# SiLPA_RF_channel_preamp.net
KiCad netlist of a schematic drawn in Altium Designer
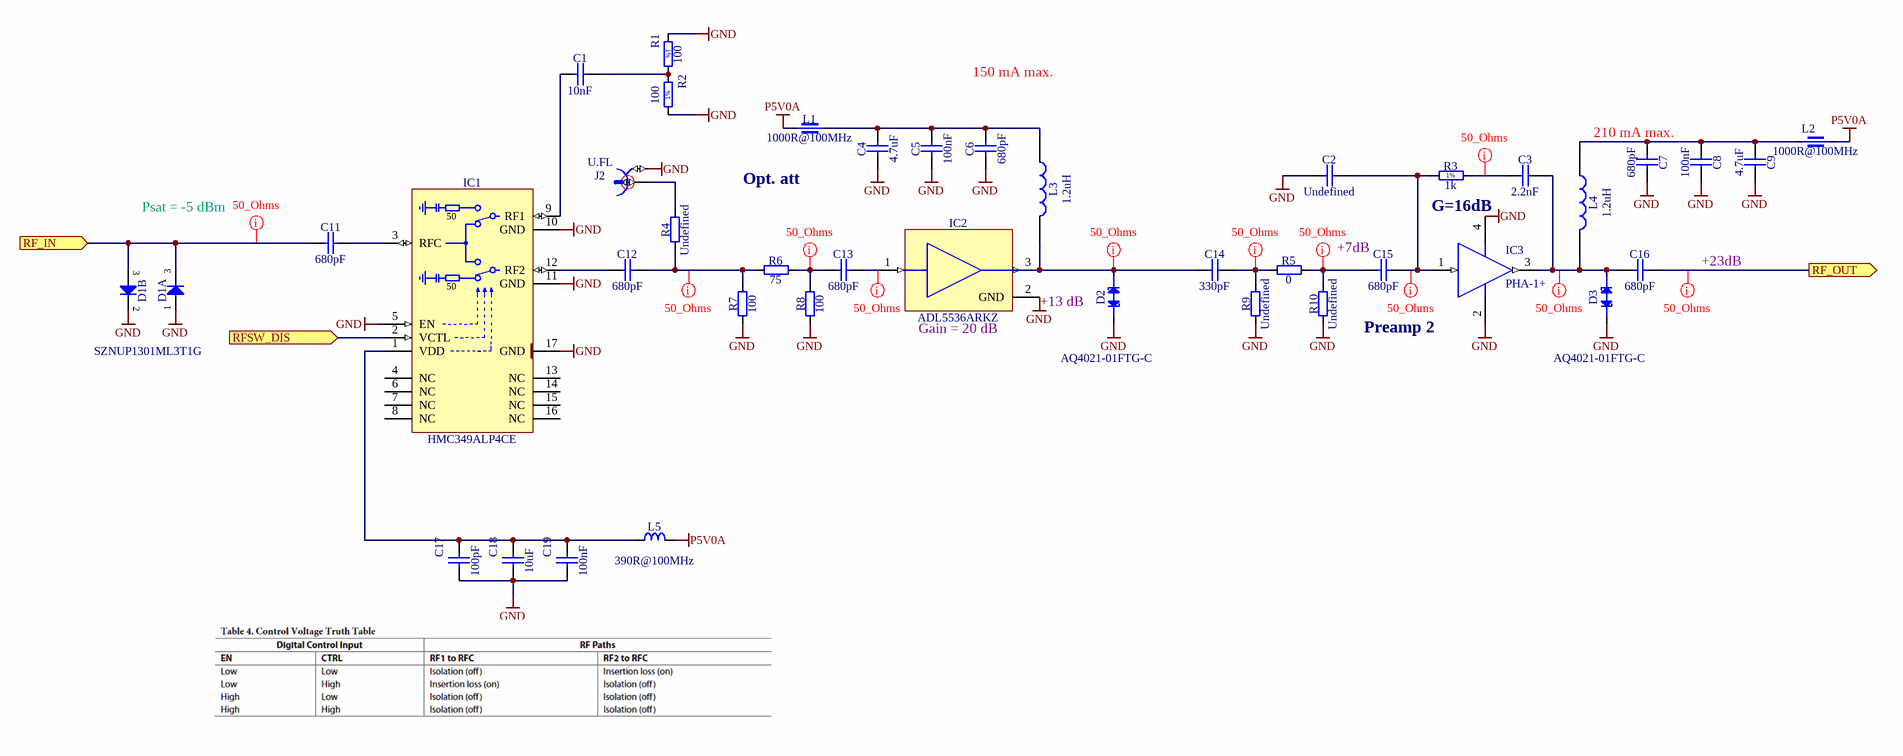
[diagram p0: SiLPA_RF_channel_preamp.SchDoc]

(export (version "E")
  (design (tool "Eeschema 10.0.6"))
  (components
    (comp (ref "C1")
      (value "10nF")
      (footprint "CAPC1005X55N")
      (description "Non-polarised capacitor")
      (fields
        (field (name "PART NUMBER") "CC0402_10NF_16V_10%_X7R")
        (field (name "VOLTAGE") "16V")
        (field (name "AUTHOR") "CERN DEM JLC")
      )
      (libsource (lib "Capacitors") (part "Capacitor - non polarized"))
    )
    (comp (ref "C2")
      (value "Undefined")
      (footprint "CAPC1608X90N")
      (description "Non-polarised capacitor")
      (fields (field (name "PART NUMBER") "CC0603_NO-VALUE") (field (name "AUTHOR") "CERN DEM MR"))
      (libsource (lib "Capacitors") (part "Capacitor - non polarized"))
    )
    (comp (ref "C3")
      (value "2.2nF")
      (footprint "CAPC1608X87N")
      (description "Non-polarised capacitor")
      (fields
        (field (name "PART NUMBER") "CC0603_2.2NF_50V_5%_C0G")
        (field (name "VOLTAGE") "50V")
        (field (name "AUTHOR") "CERN DEM JMW")
      )
      (libsource (lib "Capacitors") (part "Capacitor - non polarized"))
    )
    (comp (ref "C4")
      (value "4.7uF")
      (footprint "CAPC1709X95N")
      (description "Non-polarised capacitor")
      (fields
        (field (name "MANUFACTURER") "GENERIC")
        (field (name "MANUFACTURER PART NUMBER") "CC0603_4.7UF_16V_10%_X5R")
        (field (name "AUTHOR") "CERN DEM JLC")
      )
      (libsource (lib "Capacitors") (part "Capacitor - non polarized"))
    )
    (comp (ref "C5")
      (value "100nF")
      (footprint "CAPC1608X87N")
      (description "Non-polarised capacitor")
      (fields
        (field (name "MANUFACTURER") "GENERIC")
        (field (name "MANUFACTURER PART NUMBER") "CC0603_100NF_50V_10%_X7R")
        (field (name "AUTHOR") "CERN DEM JLC")
      )
      (libsource (lib "Capacitors") (part "Capacitor - non polarized"))
    )
    (comp (ref "C6")
      (value "680pF")
      (footprint "CAPC1608X87N")
      (description "Non-polarised capacitor")
      (fields
        (field (name "PART NUMBER") "CC0603_680PF_50V_5%_NP0")
        (field (name "VOLTAGE") "50V")
        (field (name "AUTHOR") "CERN DEM JLC")
      )
      (libsource (lib "Capacitors") (part "Capacitor - non polarized"))
    )
    (comp (ref "C7")
      (value "680pF")
      (footprint "CAPC1608X87N")
      (description "Non-polarised capacitor")
      (fields
        (field (name "MANUFACTURER") "GENERIC")
        (field (name "MANUFACTURER PART NUMBER") "CC0603_680PF_50V_5%_NP0")
        (field (name "AUTHOR") "CERN DEM JLC")
      )
      (libsource (lib "Capacitors") (part "Capacitor - non polarized"))
    )
    (comp (ref "C8")
      (value "100nF")
      (footprint "CAPC1608X87N")
      (description "Non-polarised capacitor")
      (fields
        (field (name "MANUFACTURER") "GENERIC")
        (field (name "MANUFACTURER PART NUMBER") "CC0603_100NF_50V_10%_X7R")
        (field (name "AUTHOR") "CERN DEM JLC")
      )
      (libsource (lib "Capacitors") (part "Capacitor - non polarized"))
    )
    (comp (ref "C9")
      (value "4.7uF")
      (footprint "CAPC1709X95N")
      (description "Non-polarised capacitor")
      (fields
        (field (name "MANUFACTURER") "GENERIC")
        (field (name "MANUFACTURER PART NUMBER") "CC0603_4.7UF_16V_10%_X5R")
        (field (name "AUTHOR") "CERN DEM JLC")
      )
      (libsource (lib "Capacitors") (part "Capacitor - non polarized"))
    )
    (comp (ref "C11")
      (value "680pF")
      (footprint "CAPC1608X87N")
      (description "Non-polarised capacitor")
      (fields
        (field (name "PART NUMBER") "CC0603_680PF_50V_5%_NP0")
        (field (name "VOLTAGE") "50V")
        (field (name "AUTHOR") "CERN DEM JLC")
      )
      (libsource (lib "Capacitors") (part "Capacitor - non polarized"))
    )
    (comp (ref "C12")
      (value "680pF")
      (footprint "CAPC1608X87N")
      (description "Non-polarised capacitor")
      (fields
        (field (name "PART NUMBER") "CC0603_680PF_50V_5%_NP0")
        (field (name "VOLTAGE") "50V")
        (field (name "AUTHOR") "CERN DEM JLC")
      )
      (libsource (lib "Capacitors") (part "Capacitor - non polarized"))
    )
    (comp (ref "C13")
      (value "680pF")
      (footprint "CAPC1608X87N")
      (description "Non-polarised capacitor")
      (fields
        (field (name "PART NUMBER") "CC0603_680PF_50V_5%_NP0")
        (field (name "VOLTAGE") "50V")
        (field (name "AUTHOR") "CERN DEM JLC")
      )
      (libsource (lib "Capacitors") (part "Capacitor - non polarized"))
    )
    (comp (ref "C14")
      (value "330pF")
      (footprint "CAPC1608X87N")
      (description "Non-polarised capacitor")
      (fields
        (field (name "MANUFACTURER") "GENERIC")
        (field (name "MANUFACTURER PART NUMBER") "CC0603_330PF_50V_1%_NP0")
        (field (name "AUTHOR") "CERN DEM MR")
      )
      (libsource (lib "Capacitors") (part "Capacitor - non polarized"))
    )
    (comp (ref "C15")
      (value "680pF")
      (footprint "CAPC1608X87N")
      (description "Non-polarised capacitor")
      (fields
        (field (name "MANUFACTURER") "GENERIC")
        (field (name "MANUFACTURER PART NUMBER") "CC0603_680PF_50V_5%_NP0")
        (field (name "AUTHOR") "CERN DEM JLC")
      )
      (libsource (lib "Capacitors") (part "Capacitor - non polarized"))
    )
    (comp (ref "C16")
      (value "680pF")
      (footprint "CAPC1608X87N")
      (description "Non-polarised capacitor")
      (fields
        (field (name "MANUFACTURER") "GENERIC")
        (field (name "MANUFACTURER PART NUMBER") "CC0603_680PF_50V_5%_NP0")
        (field (name "AUTHOR") "CERN DEM JLC")
      )
      (libsource (lib "Capacitors") (part "Capacitor - non polarized"))
    )
    (comp (ref "C17")
      (value "100pF")
      (footprint "CAPC1005X55N")
      (description "Non-polarised capacitor")
      (fields
        (field (name "PART NUMBER") "CC0402_100PF_50V_5%_C0G")
        (field (name "VOLTAGE") "50V")
        (field (name "AUTHOR") "CERN DEM JLC")
      )
      (libsource (lib "Capacitors") (part "Capacitor - non polarized"))
    )
    (comp (ref "C18")
      (value "10uF")
      (footprint "CAPC1608X80N")
      (description "Non-polarised capacitor")
      (fields
        (field (name "PART NUMBER") "CC0603_10UF_16V_20%_X5R")
        (field (name "VOLTAGE") "16V")
        (field (name "AUTHOR") "CERN DEM MR")
      )
      (libsource (lib "Capacitors") (part "Capacitor - non polarized"))
    )
    (comp (ref "C19")
      (value "100nF")
      (footprint "CAPC1005X55N")
      (description "Non-polarised capacitor")
      (fields
        (field (name "PART NUMBER") "CC0402_100NF_16V_10%_X5R")
        (field (name "VOLTAGE") "16V")
        (field (name "AUTHOR") "CERN DEM JLC")
      )
      (libsource (lib "Capacitors") (part "Capacitor - non polarized"))
    )
    (comp (ref "D1")
      (value "SZNUP1301ML3T1G")
      (footprint "SOT95P240X110-3N")
      (description "Low Capacitance Diode Array for ESD Protection in a Single Data Line")
      (fields (field (name "VOLTAGE") "70V") (field (name "POWER") "215mA") (field (name "AUTHOR") "GK"))
      (libsource (lib "Diodes") (part "D_TVS_SZNUP1301ML3T1G"))
    )
    (comp (ref "D2")
      (value "AQ4021-01FTG-C")
      (footprint "SOD2513X114N")
      (description "6V Bi-directional,ESD Protection for Transient Voltage Suppressor Diode")
      (fields (field (name "VOLTAGE") "6V") (field (name "POWER") "450W") (field (name "AUTHOR") "GK"))
      (libsource (lib "Diodes") (part "D_TVS_AQ4021-01FTG-C"))
    )
    (comp (ref "D3")
      (value "AQ4021-01FTG-C")
      (footprint "SOD2513X114N")
      (description "6V Bi-directional,ESD Protection for Transient Voltage Suppressor Diode")
      (fields (field (name "VOLTAGE") "6V") (field (name "POWER") "450W") (field (name "AUTHOR") "GK"))
      (libsource (lib "Diodes") (part "D_TVS_AQ4021-01FTG-C"))
    )
    (comp (ref "IC1")
      (value "HMC349ALP4CE")
      (footprint "QFN65P400X400X100-17N-S255")
      (description "DC-4GHz High Isolation SPDT Non-Reflective Switch")
      (fields (field (name "MANUFACTURER") "ANALOG DEVICES") (field (name "AUTHOR") "CERN DEM JLC"))
      (libsource (lib "ICs And Semiconductors") (part "HMC349ALP4CE"))
    )
    (comp (ref "IC2")
      (value "ADL5536ARKZ")
      (footprint "ANALOG-DEVICES_SOT-89(RK-3)")
      (description "20MHz to 1GHz IF Gain Block")
      (fields (field (name "MANUFACTURER") "ANALOG DEVICES") (field (name "AUTHOR") "CERN DEM BC"))
      (libsource (lib "ICs And Semiconductors") (part "ADL5536"))
    )
    (comp (ref "IC3")
      (value "PHA-1+")
      (footprint "MINI-CIRCUITS_DF782")
      (description "Monolithic Amplifier")
      (fields (field (name "MANUFACTURER") "MINI-CIRCUITS") (field (name "AUTHOR") "CERN DEM BC"))
      (libsource (lib "ICs And Semiconductors") (part "Monolithic Amplifier Type 1"))
    )
    (comp (ref "J2")
      (value "U.FL")
      (footprint "HIROSE_U.FL-R-SMT-1(10)")
      (fields
        (field (name "PART NUMBER") "HIROSE_U.FL-R-SMT-1(10)")
        (field (name "MANUFACTURER") "HIROSE (HRS)")
        (field (name "MANUFACTURER PART NUMBER") "U.FL-R-SMT-1(10)")
        (field (name "AUTHOR") "CERN DEM JLC")
      )
      (libsource (lib "Connectors") (part "Coax_1Male_1Shield"))
    )
    (comp (ref "L1")
      (value "1000R@100MHz")
      (footprint "INDC1608X95N")
      (fields
        (field (name "MANUFACTURER") "MURATA")
        (field (name "MANUFACTURER PART NUMBER") "BLM18HE102SN1")
        (field (name "PART NUMBER") "IND0603_MURATA_BLM18HE102SN1")
        (field (name "AUTHOR") "CERN DEM JLC")
      )
      (libsource (lib "Inductors & Transformers") (part "Ferrite Bead"))
    )
    (comp (ref "L2")
      (value "1000R@100MHz")
      (footprint "INDC1608X95N")
      (fields
        (field (name "MANUFACTURER") "MURATA")
        (field (name "MANUFACTURER PART NUMBER") "BLM18HE102SN1")
        (field (name "PART NUMBER") "IND0603_MURATA_BLM18HE102SN1")
        (field (name "AUTHOR") "CERN DEM JLC")
      )
      (libsource (lib "Inductors & Transformers") (part "Ferrite Bead"))
    )
    (comp (ref "L3")
      (value "1.2uH")
      (footprint "ADL2012S1R2MT01")
      (description "1.2uH Unshielded Drum Core, Wirewound Inductor 550 mA 500mOhm Max 0808 (2012 Metric)")
      (fields
        (field (name "PART NUMBER") "810-ADL2012S-1R2MT01")
        (field (name "POWER") "550mA")
        (field (name "AUTHORS") "skuchars")
      )
      (libsource (lib "SiLPA") (part "ADL2012S-1R2M-T01"))
    )
    (comp (ref "L4")
      (value "1.2uH")
      (footprint "ADL2012S1R2MT01")
      (description "1.2uH Unshielded Drum Core, Wirewound Inductor 550 mA 500mOhm Max 0808 (2012 Metric)")
      (fields
        (field (name "PART NUMBER") "810-ADL2012S-1R2MT01")
        (field (name "POWER") "550mA")
        (field (name "AUTHORS") "skuchars")
      )
      (libsource (lib "SiLPA") (part "ADL2012S-1R2M-T01"))
    )
    (comp (ref "L5")
      (value "390R@100MHz")
      (footprint "INDC1608X95N")
      (description "Inductor")
      (fields
        (field (name "PART NUMBER") "IND0603_TDK_MPZ1608R391A")
        (field (name "POWER") "1.2A")
        (field (name "AUTHOR") "CERN DEM JLC")
      )
      (libsource (lib "Inductors & Transformers") (part "Inductor"))
    )
    (comp (ref "R1")
      (value "100")
      (footprint "RESC1005X40N")
      (description "Resistor - 1%")
      (fields
        (field (name "PART NUMBER") "R0402_100R_1%_0.0625W_100PPM")
        (field (name "POWER") "0.0625W")
        (field (name "AUTHOR") "CERN DEM JLC")
      )
      (libsource (lib "Resistors") (part "Resistor - 1%"))
    )
    (comp (ref "R2")
      (value "100")
      (footprint "RESC1005X40N")
      (description "Resistor - 1%")
      (fields
        (field (name "PART NUMBER") "R0402_100R_1%_0.0625W_100PPM")
        (field (name "POWER") "0.0625W")
        (field (name "AUTHOR") "CERN DEM JLC")
      )
      (libsource (lib "Resistors") (part "Resistor - 1%"))
    )
    (comp (ref "R3")
      (value "1k")
      (footprint "RESC1608X55N")
      (description "Resistor - 1%")
      (fields
        (field (name "MANUFACTURER") "GENERIC")
        (field (name "MANUFACTURER PART NUMBER") "R0603_1K_1%_0.1W_100PPM")
        (field (name "AUTHOR") "CERN DEM JLC")
      )
      (libsource (lib "Resistors") (part "Resistor - 1%"))
    )
    (comp (ref "R4")
      (value "Undefined")
      (footprint "RESC1608X55N")
      (description "Resistor")
      (fields
        (field (name "MANUFACTURER PART NUMBER") "R0603_NO-VALUE")
        (field (name "AUTHOR") "CERN DEM JLC")
      )
      (libsource (lib "Resistors") (part "Resistor"))
    )
    (comp (ref "R5")
      (value "0")
      (footprint "RESC1005X40N")
      (description "Resistor")
      (fields
        (field (name "MANUFACTURER") "GENERIC")
        (field (name "MANUFACTURER PART NUMBER") "R0402_0R_JUMPER")
        (field (name "AUTHOR") "CERN DEM JLC")
      )
      (libsource (lib "Resistors") (part "Resistor"))
    )
    (comp (ref "R6")
      (value "75")
      (footprint "RESC1005X40N")
      (description "Resistor")
      (fields
        (field (name "MANUFACTURER") "GENERIC")
        (field (name "MANUFACTURER PART NUMBER") "R0402_0R_JUMPER")
        (field (name "AUTHOR") "CERN DEM JLC")
      )
      (libsource (lib "Resistors") (part "Resistor"))
    )
    (comp (ref "R7")
      (value "100")
      (footprint "RESC1608X55N")
      (description "Resistor")
      (fields
        (field (name "MANUFACTURER") "Undefined")
        (field (name "MANUFACTURER PART NUMBER") "R0603_NO-VALUE")
        (field (name "AUTHOR") "CERN DEM JLC")
      )
      (libsource (lib "Resistors") (part "Resistor"))
    )
    (comp (ref "R8")
      (value "100")
      (footprint "RESC1608X55N")
      (description "Resistor")
      (fields
        (field (name "MANUFACTURER") "Undefined")
        (field (name "MANUFACTURER PART NUMBER") "R0603_NO-VALUE")
        (field (name "AUTHOR") "CERN DEM JLC")
      )
      (libsource (lib "Resistors") (part "Resistor"))
    )
    (comp (ref "R9")
      (value "Undefined")
      (footprint "RESC1608X55N")
      (description "Resistor")
      (fields
        (field (name "MANUFACTURER PART NUMBER") "R0603_NO-VALUE")
        (field (name "AUTHOR") "CERN DEM JLC")
      )
      (libsource (lib "Resistors") (part "Resistor"))
    )
    (comp (ref "R10")
      (value "Undefined")
      (footprint "RESC1608X55N")
      (description "Resistor")
      (fields
        (field (name "MANUFACTURER PART NUMBER") "R0603_NO-VALUE")
        (field (name "AUTHOR") "CERN DEM JLC")
      )
      (libsource (lib "Resistors") (part "Resistor"))
    )
  )
  (nets
    (net (code "1") (name "/RFSW_DIS") (class "Default")
      (node (ref "IC1") (pin "2") (pinfunction "VCTL_2") (pintype "input"))
    )
    (net (code "2") (name "/RF_IN") (class "Default")
      (node (ref "C11") (pin "1") (pinfunction "1_1") (pintype "passive"))
      (node (ref "D1") (pin "3") (pinfunction "COMAC_3") (pintype "passive"))
    )
    (net (code "3") (name "/RF_OUT") (class "Default")
      (node (ref "C16") (pin "2") (pinfunction "2_2") (pintype "passive"))
    )
    (net (code "4") (name "GND") (class "Default")
      (node (ref "C17") (pin "2") (pinfunction "2_2") (pintype "passive"))
      (node (ref "C18") (pin "1") (pinfunction "1_1") (pintype "passive"))
      (node (ref "C19") (pin "1") (pinfunction "1_1") (pintype "passive"))
      (node (ref "C2") (pin "1") (pinfunction "1_1") (pintype "passive"))
      (node (ref "C4") (pin "1") (pinfunction "1_1") (pintype "passive"))
      (node (ref "C5") (pin "1") (pinfunction "1_1") (pintype "passive"))
      (node (ref "C6") (pin "1") (pinfunction "1_1") (pintype "passive"))
      (node (ref "C7") (pin "1") (pinfunction "1_1") (pintype "passive"))
      (node (ref "C8") (pin "1") (pinfunction "1_1") (pintype "passive"))
      (node (ref "C9") (pin "1") (pinfunction "1_1") (pintype "passive"))
      (node (ref "D1") (pin "1") (pinfunction "A_1") (pintype "passive"))
      (node (ref "D1") (pin "2") (pinfunction "C_2") (pintype "passive"))
      (node (ref "D2") (pin "1") (pinfunction "C_1") (pintype "passive"))
      (node (ref "D3") (pin "1") (pinfunction "C_1") (pintype "passive"))
      (node (ref "IC1") (pin "10") (pinfunction "GND_10") (pintype "power_in"))
      (node (ref "IC1") (pin "11") (pinfunction "GND_11") (pintype "power_in"))
      (node (ref "IC1") (pin "17") (pinfunction "GND_17") (pintype "power_in"))
      (node (ref "IC1") (pin "5") (pinfunction "EN_5") (pintype "input"))
      (node (ref "IC2") (pin "2") (pinfunction "GND_2") (pintype "power_in"))
      (node (ref "IC3") (pin "2") (pinfunction "GND_2") (pintype "power_in"))
      (node (ref "IC3") (pin "4") (pinfunction "GND_4") (pintype "power_in"))
      (node (ref "J2") (pin "2") (pinfunction "2_2") (pintype "bidirectional"))
      (node (ref "R1") (pin "1") (pinfunction "1_1") (pintype "passive"))
      (node (ref "R10") (pin "1") (pinfunction "1_1") (pintype "passive"))
      (node (ref "R2") (pin "1") (pinfunction "1_1") (pintype "passive"))
      (node (ref "R7") (pin "1") (pinfunction "1_1") (pintype "passive"))
      (node (ref "R8") (pin "1") (pinfunction "1_1") (pintype "passive"))
      (node (ref "R9") (pin "1") (pinfunction "1_1") (pintype "passive"))
    )
    (net (code "5") (name "Net-(C1-Pad2)") (class "Default")
      (node (ref "C1") (pin "2") (pinfunction "2_2") (pintype "passive"))
      (node (ref "R1") (pin "2") (pinfunction "2_2") (pintype "passive"))
      (node (ref "R2") (pin "2") (pinfunction "2_2") (pintype "passive"))
    )
    (net (code "6") (name "Net-(C3-Pad1)") (class "Default")
      (node (ref "C3") (pin "1") (pinfunction "1_1") (pintype "passive"))
      (node (ref "R3") (pin "2") (pinfunction "2_2") (pintype "passive"))
    )
    (net (code "7") (name "Net-(C4-Pad2)") (class "Default")
      (node (ref "C4") (pin "2") (pinfunction "2_2") (pintype "passive"))
      (node (ref "C5") (pin "2") (pinfunction "2_2") (pintype "passive"))
      (node (ref "C6") (pin "2") (pinfunction "2_2") (pintype "passive"))
      (node (ref "L1") (pin "2") (pinfunction "2_2") (pintype "passive"))
      (node (ref "L3") (pin "1") (pinfunction "1_1") (pintype "passive"))
    )
    (net (code "8") (name "Net-(C7-Pad2)") (class "Default")
      (node (ref "C7") (pin "2") (pinfunction "2_2") (pintype "passive"))
      (node (ref "C8") (pin "2") (pinfunction "2_2") (pintype "passive"))
      (node (ref "C9") (pin "2") (pinfunction "2_2") (pintype "passive"))
      (node (ref "L2") (pin "1") (pinfunction "1_1") (pintype "passive"))
      (node (ref "L4") (pin "1") (pinfunction "1_1") (pintype "passive"))
    )
    (net (code "9") (name "Net-(C12-Pad2)") (class "Default")
      (node (ref "C12") (pin "2") (pinfunction "2_2") (pintype "passive"))
      (node (ref "R4") (pin "2") (pinfunction "2_2") (pintype "passive"))
      (node (ref "R6") (pin "1") (pinfunction "1_1") (pintype "passive"))
      (node (ref "R7") (pin "2") (pinfunction "2_2") (pintype "passive"))
    )
    (net (code "10") (name "Net-(C13-Pad1)") (class "Default")
      (node (ref "C13") (pin "1") (pinfunction "1_1") (pintype "passive"))
      (node (ref "R6") (pin "2") (pinfunction "2_2") (pintype "passive"))
      (node (ref "R8") (pin "2") (pinfunction "2_2") (pintype "passive"))
    )
    (net (code "11") (name "Net-(C14-Pad2)") (class "Default")
      (node (ref "C14") (pin "2") (pinfunction "2_2") (pintype "passive"))
      (node (ref "R5") (pin "1") (pinfunction "1_1") (pintype "passive"))
      (node (ref "R9") (pin "2") (pinfunction "2_2") (pintype "passive"))
    )
    (net (code "12") (name "Net-(C15-Pad1)") (class "Default")
      (node (ref "C15") (pin "1") (pinfunction "1_1") (pintype "passive"))
      (node (ref "R10") (pin "2") (pinfunction "2_2") (pintype "passive"))
      (node (ref "R5") (pin "2") (pinfunction "2_2") (pintype "passive"))
    )
    (net (code "13") (name "Net-(D2-A)") (class "Default")
      (node (ref "C14") (pin "1") (pinfunction "1_1") (pintype "passive"))
      (node (ref "D2") (pin "2") (pinfunction "A_2") (pintype "passive"))
      (node (ref "IC2") (pin "3") (pinfunction "RFOUT_3") (pintype "output"))
      (node (ref "L3") (pin "2") (pinfunction "2_2") (pintype "passive"))
    )
    (net (code "14") (name "Net-(D3-A)") (class "Default")
      (node (ref "C16") (pin "1") (pinfunction "1_1") (pintype "passive"))
      (node (ref "C3") (pin "2") (pinfunction "2_2") (pintype "passive"))
      (node (ref "D3") (pin "2") (pinfunction "A_2") (pintype "passive"))
      (node (ref "IC3") (pin "3") (pinfunction "RF_OUT_3") (pintype "output"))
      (node (ref "L4") (pin "2") (pinfunction "2_2") (pintype "passive"))
    )
    (net (code "15") (name "Net-(IC1-RF1)") (class "Default")
      (node (ref "C1") (pin "1") (pinfunction "1_1") (pintype "passive"))
      (node (ref "IC1") (pin "9") (pinfunction "RF1_9") (pintype "bidirectional"))
    )
    (net (code "16") (name "Net-(IC1-RF2)") (class "Default")
      (node (ref "C12") (pin "1") (pinfunction "1_1") (pintype "passive"))
      (node (ref "IC1") (pin "12") (pinfunction "RF2_12") (pintype "bidirectional"))
    )
    (net (code "17") (name "Net-(IC1-RFC)") (class "Default")
      (node (ref "C11") (pin "2") (pinfunction "2_2") (pintype "passive"))
      (node (ref "IC1") (pin "3") (pinfunction "RFC_3") (pintype "bidirectional"))
    )
    (net (code "18") (name "Net-(IC1-VDD)") (class "Default")
      (node (ref "C17") (pin "1") (pinfunction "1_1") (pintype "passive"))
      (node (ref "C18") (pin "2") (pinfunction "2_2") (pintype "passive"))
      (node (ref "C19") (pin "2") (pinfunction "2_2") (pintype "passive"))
      (node (ref "IC1") (pin "1") (pinfunction "VDD_1") (pintype "power_in"))
      (node (ref "L5") (pin "1") (pinfunction "1_1") (pintype "passive"))
    )
    (net (code "19") (name "Net-(IC2-RFIN)") (class "Default")
      (node (ref "C13") (pin "2") (pinfunction "2_2") (pintype "passive"))
      (node (ref "IC2") (pin "1") (pinfunction "RFIN_1") (pintype "input"))
    )
    (net (code "20") (name "Net-(IC3-RF_IN)") (class "Default")
      (node (ref "C15") (pin "2") (pinfunction "2_2") (pintype "passive"))
      (node (ref "C2") (pin "2") (pinfunction "2_2") (pintype "passive"))
      (node (ref "IC3") (pin "1") (pinfunction "RF_IN_1") (pintype "input"))
      (node (ref "R3") (pin "1") (pinfunction "1_1") (pintype "passive"))
    )
    (net (code "21") (name "Net-(J2-Pad1)") (class "Default")
      (node (ref "J2") (pin "1") (pinfunction "1_1") (pintype "bidirectional"))
      (node (ref "R4") (pin "1") (pinfunction "1_1") (pintype "passive"))
    )
    (net (code "22") (name "P5V0A") (class "Default")
      (node (ref "L1") (pin "1") (pinfunction "1_1") (pintype "passive"))
      (node (ref "L2") (pin "2") (pinfunction "2_2") (pintype "passive"))
      (node (ref "L5") (pin "2") (pinfunction "2_2") (pintype "passive"))
    )
    (net (code "23") (name "unconnected-(IC1-NC-Pad4)") (class "Default")
      (node (ref "IC1") (pin "4") (pinfunction "NC_4") (pintype "passive"))
    )
    (net (code "24") (name "unconnected-(IC1-NC-Pad6)") (class "Default")
      (node (ref "IC1") (pin "6") (pinfunction "NC_6") (pintype "passive"))
    )
    (net (code "25") (name "unconnected-(IC1-NC-Pad7)") (class "Default")
      (node (ref "IC1") (pin "7") (pinfunction "NC_7") (pintype "passive"))
    )
    (net (code "26") (name "unconnected-(IC1-NC-Pad8)") (class "Default")
      (node (ref "IC1") (pin "8") (pinfunction "NC_8") (pintype "passive"))
    )
    (net (code "27") (name "unconnected-(IC1-NC-Pad13)") (class "Default")
      (node (ref "IC1") (pin "13") (pinfunction "NC_13") (pintype "passive"))
    )
    (net (code "28") (name "unconnected-(IC1-NC-Pad14)") (class "Default")
      (node (ref "IC1") (pin "14") (pinfunction "NC_14") (pintype "passive"))
    )
    (net (code "29") (name "unconnected-(IC1-NC-Pad15)") (class "Default")
      (node (ref "IC1") (pin "15") (pinfunction "NC_15") (pintype "passive"))
    )
    (net (code "30") (name "unconnected-(IC1-NC-Pad16)") (class "Default")
      (node (ref "IC1") (pin "16") (pinfunction "NC_16") (pintype "passive"))
    )
  )
)
